# Mako_DSP_USB_R2_1.net
KiCad netlist of a schematic drawn in Altium Designer
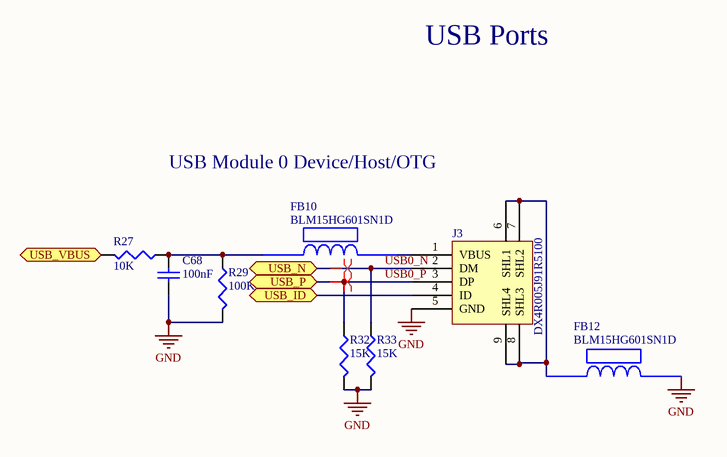
[diagram p0: Mako DSP USB R2.1.SchDoc]

(export (version "E")
  (design (tool "Eeschema 10.0.6"))
  (components
    (comp (ref "C68")
      (value "100nF")
      (footprint "1608[0603]")
      (description "Capacitor (Semiconductor SIM Model)")
      (fields (field (name "Comment") "Cap Semi") (field (name "PUBLISHER") "Altium Limited"))
      (libsource (lib "Miscellaneous Devices") (part "Cap Semi"))
    )
    (comp (ref "FB10")
      (value "BLM15HG601SN1D")
      (footprint "BLM18PG121SN1D")
      (libsource (lib "AHD Part Library") (part "BLM15HG601SN1D"))
    )
    (comp (ref "FB12")
      (value "BLM15HG601SN1D")
      (footprint "BLM18PG121SN1D")
      (libsource (lib "AHD Part Library") (part "BLM15HG601SN1D"))
    )
    (comp (ref "J3")
      (value "DX4R005J91R5100")
      (footprint "Micro USB Circular Holes Only")
      (description "Micro USB Jack B")
      (libsource (lib "Adams Altium Library") (part "Micro USB"))
    )
    (comp (ref "R27")
      (value "10K")
      (footprint "J1-0603")
      (description "Resistor")
      (fields (field (name "Comment") "Res3") (field (name "PUBLISHER") "Altium Limited"))
      (libsource (lib "Miscellaneous Devices") (part "Res3"))
    )
    (comp (ref "R29")
      (value "100K")
      (footprint "J1-0603")
      (description "Resistor")
      (fields (field (name "Comment") "Res3") (field (name "PUBLISHER") "Altium Limited"))
      (libsource (lib "Miscellaneous Devices") (part "Res3"))
    )
    (comp (ref "R32")
      (value "15K")
      (footprint "J1-0603")
      (description "Resistor")
      (fields (field (name "Comment") "Res3") (field (name "PUBLISHER") "Altium Limited"))
      (libsource (lib "Miscellaneous Devices") (part "Res3"))
    )
    (comp (ref "R33")
      (value "15K")
      (footprint "J1-0603")
      (description "Resistor")
      (fields (field (name "Comment") "Res3") (field (name "PUBLISHER") "Altium Limited"))
      (libsource (lib "Miscellaneous Devices") (part "Res3"))
    )
  )
  (nets
    (net (code "1") (name "/USB0_N") (class "Default")
      (node (ref "J3") (pin "2") (pinfunction "DM_2") (pintype "passive"))
      (node (ref "R33") (pin "1") (pinfunction "1_1") (pintype "passive"))
    )
    (net (code "2") (name "/USB0_P") (class "Default")
      (node (ref "J3") (pin "3") (pinfunction "DP_3") (pintype "passive"))
      (node (ref "R32") (pin "1") (pinfunction "1_1") (pintype "passive"))
    )
    (net (code "3") (name "/USB_ID") (class "Default")
      (node (ref "J3") (pin "4") (pinfunction "ID_4") (pintype "passive"))
    )
    (net (code "4") (name "/USB_VBUS") (class "Default")
      (node (ref "R27") (pin "2") (pinfunction "2_2") (pintype "passive"))
    )
    (net (code "5") (name "GND") (class "Default")
      (node (ref "C68") (pin "1") (pinfunction "1_1") (pintype "passive"))
      (node (ref "FB12") (pin "2") (pinfunction "2_2") (pintype "passive"))
      (node (ref "J3") (pin "5") (pinfunction "GND_5") (pintype "passive"))
      (node (ref "R29") (pin "2") (pinfunction "2_2") (pintype "passive"))
      (node (ref "R32") (pin "2") (pinfunction "2_2") (pintype "passive"))
      (node (ref "R33") (pin "2") (pinfunction "2_2") (pintype "passive"))
    )
    (net (code "6") (name "Net-(C68-Pad2)") (class "Default")
      (node (ref "C68") (pin "2") (pinfunction "2_2") (pintype "passive"))
      (node (ref "FB10") (pin "1") (pinfunction "1_1") (pintype "passive"))
      (node (ref "R27") (pin "1") (pinfunction "1_1") (pintype "passive"))
      (node (ref "R29") (pin "1") (pinfunction "1_1") (pintype "passive"))
    )
    (net (code "7") (name "Net-(J3-SHL1)") (class "Default")
      (node (ref "FB12") (pin "1") (pinfunction "1_1") (pintype "passive"))
      (node (ref "J3") (pin "6") (pinfunction "SHL1_6") (pintype "passive"))
      (node (ref "J3") (pin "7") (pinfunction "SHL2_7") (pintype "passive"))
      (node (ref "J3") (pin "8") (pinfunction "SHL3_8") (pintype "passive"))
      (node (ref "J3") (pin "9") (pinfunction "SHL4_9") (pintype "passive"))
    )
    (net (code "8") (name "Net-(J3-VBUS)") (class "Default")
      (node (ref "FB10") (pin "2") (pinfunction "2_2") (pintype "passive"))
      (node (ref "J3") (pin "1") (pinfunction "VBUS_1") (pintype "passive"))
    )
  )
)
